# 04_Mechanical.net
KiCad netlist of a schematic drawn in Altium Designer
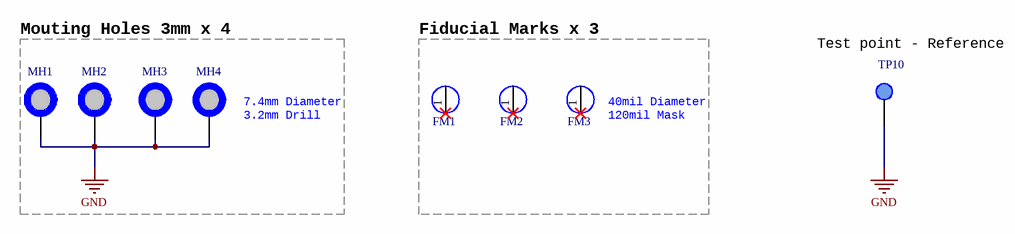
[diagram p0: 04.Mechanical.SchDoc]

(export (version "E")
  (design (tool "Eeschema 10.0.6"))
  (components
    (comp (ref "FM1")
      (value "FM")
      (footprint "FM")
      (description "Fiducial mark")
      (libsource (lib "Altium_Main_Library") (part "FM"))
    )
    (comp (ref "FM2")
      (value "FM")
      (footprint "FM")
      (description "Fiducial mark")
      (libsource (lib "Altium_Main_Library") (part "FM"))
    )
    (comp (ref "FM3")
      (value "FM")
      (footprint "FM")
      (description "Fiducial mark")
      (libsource (lib "Altium_Main_Library") (part "FM"))
    )
    (comp (ref "MH1")
      (value "MH_7.4MMC_3.2MMD")
      (footprint "MECHANICAL_M3")
      (description "Mounting Hole 7.4mm Diameter, 3.2mm Drill")
      (libsource (lib "Altium_Main_Library") (part "Mounting_Hole2"))
    )
    (comp (ref "MH2")
      (value "MH_7.4MMC_3.2MMD")
      (footprint "MECHANICAL_M3")
      (description "Mounting Hole 7.4mm Diameter, 3.2mm Drill")
      (libsource (lib "Altium_Main_Library") (part "Mounting_Hole2"))
    )
    (comp (ref "MH3")
      (value "MH_7.4MMC_3.2MMD")
      (footprint "MECHANICAL_M3")
      (description "Mounting Hole 7.4mm Diameter, 3.2mm Drill")
      (libsource (lib "Altium_Main_Library") (part "Mounting_Hole2"))
    )
    (comp (ref "MH4")
      (value "MH_7.4MMC_3.2MMD")
      (footprint "MECHANICAL_M3")
      (description "Mounting Hole 7.4mm Diameter, 3.2mm Drill")
      (libsource (lib "Altium_Main_Library") (part "Mounting_Hole2"))
    )
    (comp (ref "TP10")
      (value "~")
      (footprint "tp")
      (description "Test Point")
      (libsource (lib "Altium_Main_Library") (part "TP"))
    )
  )
  (nets
    (net (code "1") (name "GND") (class "Default")
      (node (ref "MH1") (pin "1") (pinfunction "1_1") (pintype "passive"))
      (node (ref "MH2") (pin "1") (pinfunction "1_1") (pintype "passive"))
      (node (ref "MH3") (pin "1") (pinfunction "1_1") (pintype "passive"))
      (node (ref "MH4") (pin "1") (pinfunction "1_1") (pintype "passive"))
      (node (ref "TP10") (pin "1") (pinfunction "___TP_1") (pintype "passive"))
    )
    (net (code "2") (name "unconnected-(FM1-FM-Pad1)") (class "Default")
      (node (ref "FM1") (pin "1") (pinfunction "FM_1") (pintype "passive+no_connect"))
    )
    (net (code "3") (name "unconnected-(FM2-FM-Pad1)") (class "Default")
      (node (ref "FM2") (pin "1") (pinfunction "FM_1") (pintype "passive+no_connect"))
    )
    (net (code "4") (name "unconnected-(FM3-FM-Pad1)") (class "Default")
      (node (ref "FM3") (pin "1") (pinfunction "FM_1") (pintype "passive+no_connect"))
    )
  )
)
